# design.net
KiCad netlist of a schematic drawn in Altium Designer
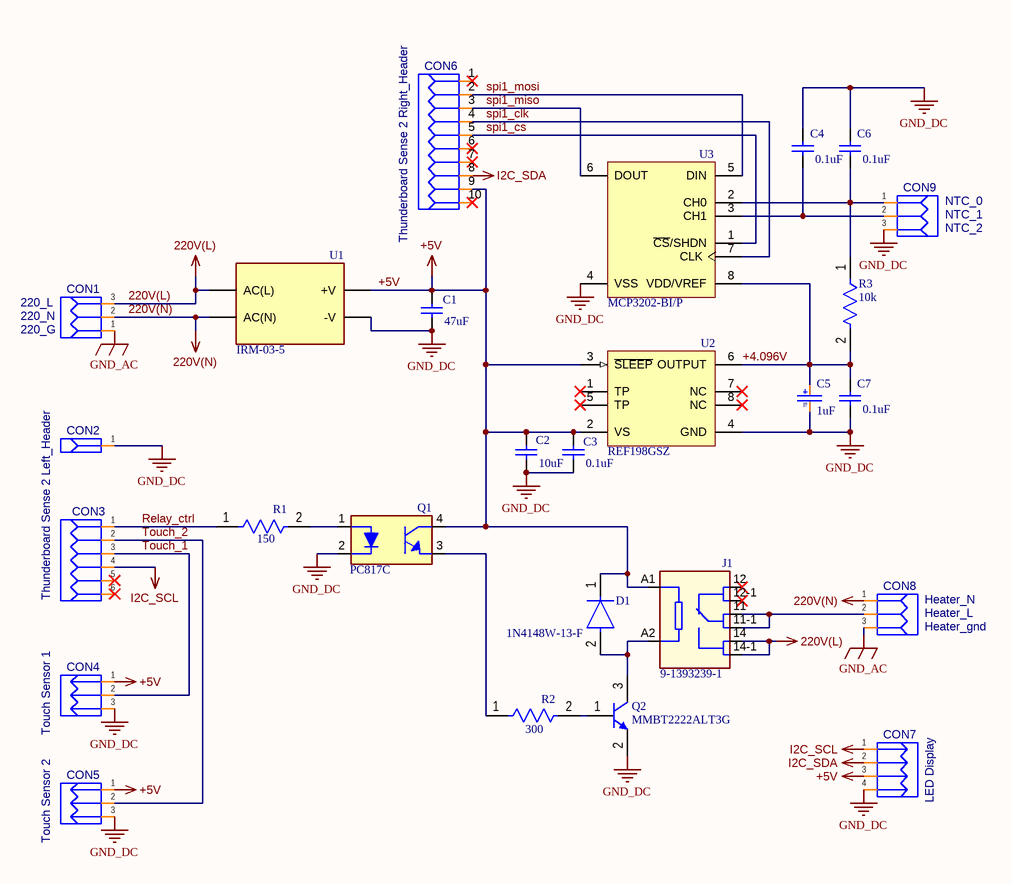
[diagram p0: Схема принципиальная.SchDoc]

(export (version "E")
  (design (tool "Eeschema 10.0.6"))
  (components
    (comp (ref "C1")
      (value "47uF")
      (footprint "MURA-1210_H_2.7_L")
      (description "Cap Ceramic, 47 uF, +/- 10%, -55 to 85 degC, 2-Pin SMD (1210), RoHS, Tape and Reel")
      (fields (field (name "TOLERANCE") "±10%") (field (name "MANUFACTURER") "Murata"))
      (libsource (lib "Altium Content Vault") (part "CAP-NP-2"))
    )
    (comp (ref "C2")
      (value "10uF")
      (footprint "CAPC2013X135X45ML10T25")
      (description "GRM21BR61E106KA73L\r\n10uF, +/- 10%, 25 V, 0805")
      (fields (field (name "MANUFACTURER") "Murata"))
      (libsource (lib "Altium Content Vault") (part "CAP-NP-2"))
    )
    (comp (ref "C3")
      (value "0.1uF")
      (footprint "CAPC2013X140X45NL15T25")
      (description "GRM21BR71H104K\r\n0.1 мкФ X7R 10% 50В 0805")
      (fields (field (name "PART NUMBER") "GRM21BR71C475KA73L") (field (name "MANUFACTURER") "Murata"))
      (libsource (lib "Altium Content Vault") (part "CAP"))
    )
    (comp (ref "C4")
      (value "0.1uF")
      (footprint "CAPC2013X140X45NL15T25")
      (description "GRM21BR71H104K\r\n0.1 мкФ X7R 10% 50В 0805")
      (fields (field (name "PART NUMBER") "GRM21BR71C475KA73L") (field (name "MANUFACTURER") "Murata"))
      (libsource (lib "Altium Content Vault") (part "CAP"))
    )
    (comp (ref "C5")
      (value "1uF")
      (footprint "TANTAL_B")
      (description "TANTAL TECAP1/50V B, 10%")
      (fields (field (name "PUBLISHER") "Catcatcat Electronics"))
      (libsource (lib "CapacitorElectrolytic") (part "_TANTAL-B"))
    )
    (comp (ref "C6")
      (value "0.1uF")
      (footprint "CAPC2013X140X45NL15T25")
      (description "GRM21BR71H104K\r\n0.1 мкФ X7R 10% 50В 0805")
      (fields (field (name "PART NUMBER") "GRM21BR71C475KA73L") (field (name "MANUFACTURER") "Murata"))
      (libsource (lib "Altium Content Vault") (part "CAP"))
    )
    (comp (ref "C7")
      (value "0.1uF")
      (footprint "CAPC2013X140X45NL15T25")
      (description "GRM21BR71H104K\r\n0.1 мкФ X7R 10% 50В 0805")
      (fields (field (name "PART NUMBER") "GRM21BR71C475KA73L") (field (name "MANUFACTURER") "Murata"))
      (libsource (lib "Altium Content Vault") (part "CAP"))
    )
    (comp (ref "CON1")
      (value "DG128-3")
      (footprint "DG129-5.08-3")
      (fields (field (name "PUBLISHER") "Catcatcat Electronics"))
      (libsource (lib "Connectors") (part "DG129-5.08-3"))
    )
    (comp (ref "CON2")
      (value "PBS-01")
      (footprint "PBS-01")
      (description "2.54mm")
      (fields (field (name "PUBLISHER") "Catcatcat Electronics"))
      (libsource (lib "Connectors") (part "PBS-01"))
    )
    (comp (ref "CON3")
      (value "PBS-06")
      (footprint "PBS-06")
      (description "2.54mm")
      (fields (field (name "PUBLISHER") "Catcatcat Electronics"))
      (libsource (lib "Connectors") (part "PBS-06"))
    )
    (comp (ref "CON4")
      (value "PLS-03")
      (footprint "PLS-03")
      (description "2.54 mm")
      (fields (field (name "PUBLISHER") "Catcatcat Electronics"))
      (libsource (lib "Connectors") (part "PLS-03"))
    )
    (comp (ref "CON5")
      (value "PLS-03")
      (footprint "PLS-03")
      (description "2.54 mm")
      (fields (field (name "PUBLISHER") "Catcatcat Electronics"))
      (libsource (lib "Connectors") (part "PLS-03"))
    )
    (comp (ref "CON6")
      (value "PBS-10")
      (footprint "PBS-10")
      (description "2.54mm")
      (fields (field (name "PUBLISHER") "Catcatcat Electronics"))
      (libsource (lib "Connectors") (part "PBS-10"))
    )
    (comp (ref "CON7")
      (value "PLS-04")
      (footprint "PLS-04")
      (description "2.54 mm")
      (fields (field (name "PUBLISHER") "Catcatcat Electronics"))
      (libsource (lib "Connectors") (part "PLS-04"))
    )
    (comp (ref "CON8")
      (value "DG128-3")
      (footprint "DG129-5.08-3")
      (fields (field (name "PUBLISHER") "Catcatcat Electronics"))
      (libsource (lib "Connectors") (part "DG129-5.08-3"))
    )
    (comp (ref "CON9")
      (value "DG128-3")
      (footprint "DG129-5.08-3")
      (fields (field (name "PUBLISHER") "Catcatcat Electronics"))
      (libsource (lib "Connectors") (part "DG129-5.08-3"))
    )
    (comp (ref "D1")
      (value "1N4148W-13-F")
      (footprint "FP-SOD123-MFG")
      (description "DIODE GEN PURP 100V 150MA SOD123")
      (fields
        (field (name "OCTOPART") "https://octopart.com/1n4148w-13-f-diodes+inc.-2359612")
        (field (name "MANUFACTURER") "Diodes Inc.")
      )
      (libsource (lib "Altium Content Vault") (part "d7152d700b627762746794eb795d46e"))
    )
    (comp (ref "J1")
      (value "9-1393239-1")
      (footprint "RT314005:RELAY_9-1393239-1")
      (description "RELAY GEN PURPOSE SPDT 16A 5V")
      (fields (field (name "MF") "{'manufacturer': u'TE Connectivity'}"))
      (libsource (lib "RT314005") (part "9-1393239-1"))
    )
    (comp (ref "Q1")
      (value "PC817C")
      (footprint "PC817C:DIP762W50P254L650H458Q4B")
      (description "High Density Mounting Type Photocoupler")
      (fields (field (name "MF") "{'manufacturer': u'Taiwan Semiconductor'}"))
      (libsource (lib "PC817C") (part "PC817C"))
    )
    (comp (ref "Q2")
      (value "MMBT2222ALT3G")
      (footprint "ONSC-SOT-23-3-318-08_V")
      (description "General Purpose Transistor, NPN Silicon, 3-Pin SOT-23, Pb-Free, Tape and Reel")
      (fields (field (name "MANUFACTURER") "On Semiconductor"))
      (libsource (lib "Altium Content Vault") (part "ONSC-NPN-B1E2C3-3"))
    )
    (comp (ref "R1")
      (value "150")
      (footprint "FP-CR0805-IPC_C")
      (description "0805 150Ω 0.125W 1%")
      (fields (field (name "TOLERANCE") "1%"))
      (libsource (lib "Altium Content Vault") (part "1029c3af85768c4190bb7ad29bc67b5"))
    )
    (comp (ref "R2")
      (value "300")
      (footprint "FP-CR0805-IPC_C")
      (description "0805 300kΩ 0.125W 1%")
      (fields (field (name "TOLERANCE") "1%"))
      (libsource (lib "Altium Content Vault") (part "1029c3af85768c4190bb7ad29bc67b5"))
    )
    (comp (ref "R3")
      (value "10k")
      (footprint "FP-CRCW1206-e3-IPC_C")
      (description "10kΩ, 1%, 0.25W 1206")
      (fields (field (name "TOLERANCE") "1%"))
      (libsource (lib "Altium Content Vault") (part "1029c3af85768c4190bb7ad29bc67b5"))
    )
    (comp (ref "U1")
      (value "IRM-03-5")
      (footprint "IRM-03-5:footprint_IRM-03-5")
      (description "AC-DC Single output Encapsulated power supply; Output 5Vdc at 0.6A; PCB mount, miniature size")
      (fields (field (name "MF") "{'manufacturer': u'MEAN WELL'}"))
      (libsource (lib "IRM-03-5") (part "IRM-03-5"))
    )
    (comp (ref "U2")
      (value "REF198GSZ")
      (footprint "ADI-R-8_M")
      (fields (field (name "MANUFACTURER") "Analog Devices"))
      (libsource (lib "Altium Content Vault") (part "ADI-REF19X-8"))
    )
    (comp (ref "U3")
      (value "MCP3202-BI/P")
      (footprint "PDIP300-P8")
      (libsource (lib "Altium Content Vault") (part "CON-ADC-MCP3002-8"))
    )
  )
  (nets
    (net (code "1") (name "+5V") (class "Default")
      (node (ref "C1") (pin "2") (pinfunction "2_2") (pintype "passive"))
      (node (ref "C2") (pin "2") (pinfunction "2_2") (pintype "passive"))
      (node (ref "C3") (pin "2") (pinfunction "2_2") (pintype "passive"))
      (node (ref "CON4") (pin "1") (pinfunction "1_1") (pintype "passive"))
      (node (ref "CON5") (pin "1") (pinfunction "1_1") (pintype "passive"))
      (node (ref "CON6") (pin "9") (pinfunction "9_9") (pintype "passive"))
      (node (ref "CON7") (pin "3") (pinfunction "3_3") (pintype "passive"))
      (node (ref "D1") (pin "1") (pinfunction "C_1") (pintype "passive"))
      (node (ref "J1") (pin "A1") (pinfunction "A1_A1") (pintype "passive"))
      (node (ref "Q1") (pin "4") (pinfunction "4_4") (pintype "passive"))
      (node (ref "U1") (pin "+V") (pinfunction "+V_+V") (pintype "power_in"))
      (node (ref "U2") (pin "2") (pinfunction "VS_2") (pintype "power_in"))
      (node (ref "U2") (pin "3") (pinfunction "~{SLEEP}_3") (pintype "input"))
    )
    (net (code "2") (name "/+4.096V") (class "Default")
      (node (ref "C5") (pin "1") (pintype "passive"))
      (node (ref "C7") (pin "2") (pinfunction "2_2") (pintype "passive"))
      (node (ref "R3") (pin "2") (pinfunction "2_2") (pintype "passive"))
      (node (ref "U2") (pin "6") (pinfunction "OUTPUT_6") (pintype "power_in"))
      (node (ref "U3") (pin "8") (pinfunction "VDD/VREF_8") (pintype "power_in"))
    )
    (net (code "3") (name "/Relay_ctrl") (class "Default")
      (node (ref "CON3") (pin "1") (pinfunction "1_1") (pintype "passive"))
      (node (ref "R1") (pin "1") (pinfunction "1_1") (pintype "passive"))
    )
    (net (code "4") (name "/Touch_1") (class "Default")
      (node (ref "CON3") (pin "3") (pinfunction "3_3") (pintype "passive"))
      (node (ref "CON4") (pin "2") (pinfunction "2_2") (pintype "passive"))
    )
    (net (code "5") (name "/Touch_2") (class "Default")
      (node (ref "CON3") (pin "2") (pinfunction "2_2") (pintype "passive"))
      (node (ref "CON5") (pin "2") (pinfunction "2_2") (pintype "passive"))
    )
    (net (code "6") (name "/spi1_clk") (class "Default")
      (node (ref "CON6") (pin "4") (pinfunction "4_4") (pintype "passive"))
      (node (ref "U3") (pin "7") (pinfunction "CLK_7") (pintype "passive"))
    )
    (net (code "7") (name "/spi1_cs") (class "Default")
      (node (ref "CON6") (pin "5") (pinfunction "5_5") (pintype "passive"))
      (node (ref "U3") (pin "1") (pinfunction "~{CS}/SHDN_1") (pintype "passive"))
    )
    (net (code "8") (name "/spi1_miso") (class "Default")
      (node (ref "CON6") (pin "3") (pinfunction "3_3") (pintype "passive"))
      (node (ref "U3") (pin "6") (pinfunction "DOUT_6") (pintype "passive"))
    )
    (net (code "9") (name "/spi1_mosi") (class "Default")
      (node (ref "CON6") (pin "2") (pinfunction "2_2") (pintype "passive"))
      (node (ref "U3") (pin "5") (pinfunction "DIN_5") (pintype "passive"))
    )
    (net (code "10") (name "220V(L)") (class "Default")
      (node (ref "CON1") (pin "3") (pinfunction "3_3") (pintype "passive"))
      (node (ref "J1") (pin "14") (pinfunction "14_14") (pintype "passive"))
      (node (ref "J1") (pin "14-1") (pinfunction "14_14-1") (pintype "passive"))
      (node (ref "U1") (pin "AC/L") (pinfunction "AC(L)_AC/L") (pintype "power_in"))
    )
    (net (code "11") (name "220V(N)") (class "Default")
      (node (ref "CON1") (pin "2") (pinfunction "2_2") (pintype "passive"))
      (node (ref "CON8") (pin "1") (pinfunction "1_1") (pintype "passive"))
      (node (ref "U1") (pin "AC/N") (pinfunction "AC(N)_AC/N") (pintype "power_in"))
    )
    (net (code "12") (name "GND_AC") (class "Default")
      (node (ref "CON1") (pin "1") (pinfunction "1_1") (pintype "passive"))
      (node (ref "CON8") (pin "3") (pinfunction "3_3") (pintype "passive"))
    )
    (net (code "13") (name "GND_DC") (class "Default")
      (node (ref "C1") (pin "1") (pinfunction "1_1") (pintype "passive"))
      (node (ref "C2") (pin "1") (pinfunction "1_1") (pintype "passive"))
      (node (ref "C3") (pin "1") (pinfunction "1_1") (pintype "passive"))
      (node (ref "C4") (pin "2") (pinfunction "2_2") (pintype "passive"))
      (node (ref "C5") (pin "2") (pintype "passive"))
      (node (ref "C6") (pin "2") (pinfunction "2_2") (pintype "passive"))
      (node (ref "C7") (pin "1") (pinfunction "1_1") (pintype "passive"))
      (node (ref "CON2") (pin "1") (pinfunction "1_1") (pintype "passive"))
      (node (ref "CON4") (pin "3") (pinfunction "3_3") (pintype "passive"))
      (node (ref "CON5") (pin "3") (pinfunction "3_3") (pintype "passive"))
      (node (ref "CON7") (pin "4") (pinfunction "4_4") (pintype "passive"))
      (node (ref "CON9") (pin "3") (pinfunction "3_3") (pintype "passive"))
      (node (ref "Q1") (pin "2") (pinfunction "2_2") (pintype "passive"))
      (node (ref "Q2") (pin "2") (pinfunction "E_2") (pintype "passive"))
      (node (ref "U1") (pin "-V") (pinfunction "-V_-V") (pintype "power_in"))
      (node (ref "U2") (pin "4") (pinfunction "GND_4") (pintype "power_in"))
      (node (ref "U3") (pin "4") (pinfunction "VSS_4") (pintype "power_in"))
    )
    (net (code "14") (name "I2C_SCL") (class "Default")
      (node (ref "CON3") (pin "4") (pinfunction "4_4") (pintype "passive"))
      (node (ref "CON7") (pin "1") (pinfunction "1_1") (pintype "passive"))
    )
    (net (code "15") (name "I2C_SDA") (class "Default")
      (node (ref "CON6") (pin "8") (pinfunction "8_8") (pintype "passive"))
      (node (ref "CON7") (pin "2") (pinfunction "2_2") (pintype "passive"))
    )
    (net (code "16") (name "Net-(CON8-Pad2)") (class "Default")
      (node (ref "CON8") (pin "2") (pinfunction "2_2") (pintype "passive"))
      (node (ref "J1") (pin "11") (pinfunction "11_11") (pintype "passive"))
      (node (ref "J1") (pin "11-1") (pinfunction "11_11-1") (pintype "passive"))
    )
    (net (code "17") (name "Net-(D1-A)") (class "Default")
      (node (ref "D1") (pin "2") (pinfunction "A_2") (pintype "passive"))
      (node (ref "J1") (pin "A2") (pinfunction "A2_A2") (pintype "passive"))
      (node (ref "Q2") (pin "3") (pinfunction "C_3") (pintype "passive"))
    )
    (net (code "18") (name "Net-(Q1-Pad1)") (class "Default")
      (node (ref "Q1") (pin "1") (pinfunction "1_1") (pintype "passive"))
      (node (ref "R1") (pin "2") (pinfunction "2_2") (pintype "passive"))
    )
    (net (code "19") (name "Net-(Q1-Pad3)") (class "Default")
      (node (ref "Q1") (pin "3") (pinfunction "3_3") (pintype "passive"))
      (node (ref "R2") (pin "1") (pinfunction "1_1") (pintype "passive"))
    )
    (net (code "20") (name "Net-(Q2-B)") (class "Default")
      (node (ref "Q2") (pin "1") (pinfunction "B_1") (pintype "passive"))
      (node (ref "R2") (pin "2") (pinfunction "2_2") (pintype "passive"))
    )
    (net (code "21") (name "Net-(U3-CH0)") (class "Default")
      (node (ref "C6") (pin "1") (pinfunction "1_1") (pintype "passive"))
      (node (ref "CON9") (pin "1") (pinfunction "1_1") (pintype "passive"))
      (node (ref "R3") (pin "1") (pinfunction "1_1") (pintype "passive"))
      (node (ref "U3") (pin "2") (pinfunction "CH0_2") (pintype "passive"))
    )
    (net (code "22") (name "Net-(U3-CH1)") (class "Default")
      (node (ref "C4") (pin "1") (pinfunction "1_1") (pintype "passive"))
      (node (ref "CON9") (pin "2") (pinfunction "2_2") (pintype "passive"))
      (node (ref "U3") (pin "3") (pinfunction "CH1_3") (pintype "passive"))
    )
    (net (code "23") (name "unconnected-(CON3-Pad5)") (class "Default")
      (node (ref "CON3") (pin "5") (pinfunction "5_5") (pintype "passive+no_connect"))
    )
    (net (code "24") (name "unconnected-(CON3-Pad6)") (class "Default")
      (node (ref "CON3") (pin "6") (pinfunction "6_6") (pintype "passive+no_connect"))
    )
    (net (code "25") (name "unconnected-(CON6-Pad1)") (class "Default")
      (node (ref "CON6") (pin "1") (pinfunction "1_1") (pintype "passive+no_connect"))
    )
    (net (code "26") (name "unconnected-(CON6-Pad6)") (class "Default")
      (node (ref "CON6") (pin "6") (pinfunction "6_6") (pintype "passive+no_connect"))
    )
    (net (code "27") (name "unconnected-(CON6-Pad7)") (class "Default")
      (node (ref "CON6") (pin "7") (pinfunction "7_7") (pintype "passive+no_connect"))
    )
    (net (code "28") (name "unconnected-(CON6-Pad10)") (class "Default")
      (node (ref "CON6") (pin "10") (pinfunction "10_10") (pintype "passive+no_connect"))
    )
    (net (code "29") (name "unconnected-(J1-12-Pad12-1)") (class "Default")
      (node (ref "J1") (pin "12-1") (pinfunction "12_12-1") (pintype "passive+no_connect"))
    )
    (net (code "30") (name "unconnected-(J1-Pad12)") (class "Default")
      (node (ref "J1") (pin "12") (pinfunction "12_12") (pintype "passive+no_connect"))
    )
    (net (code "31") (name "unconnected-(U2-NC-Pad7)") (class "Default")
      (node (ref "U2") (pin "7") (pinfunction "NC_7") (pintype "passive+no_connect"))
    )
    (net (code "32") (name "unconnected-(U2-NC-Pad8)") (class "Default")
      (node (ref "U2") (pin "8") (pinfunction "NC_8") (pintype "passive+no_connect"))
    )
    (net (code "33") (name "unconnected-(U2-TP-Pad1)") (class "Default")
      (node (ref "U2") (pin "1") (pinfunction "TP_1") (pintype "passive+no_connect"))
    )
    (net (code "34") (name "unconnected-(U2-TP-Pad5)") (class "Default")
      (node (ref "U2") (pin "5") (pinfunction "TP_5") (pintype "passive+no_connect"))
    )
  )
)
